# ColorfulTunes.net
KiCad netlist of a schematic drawn in EAGLE
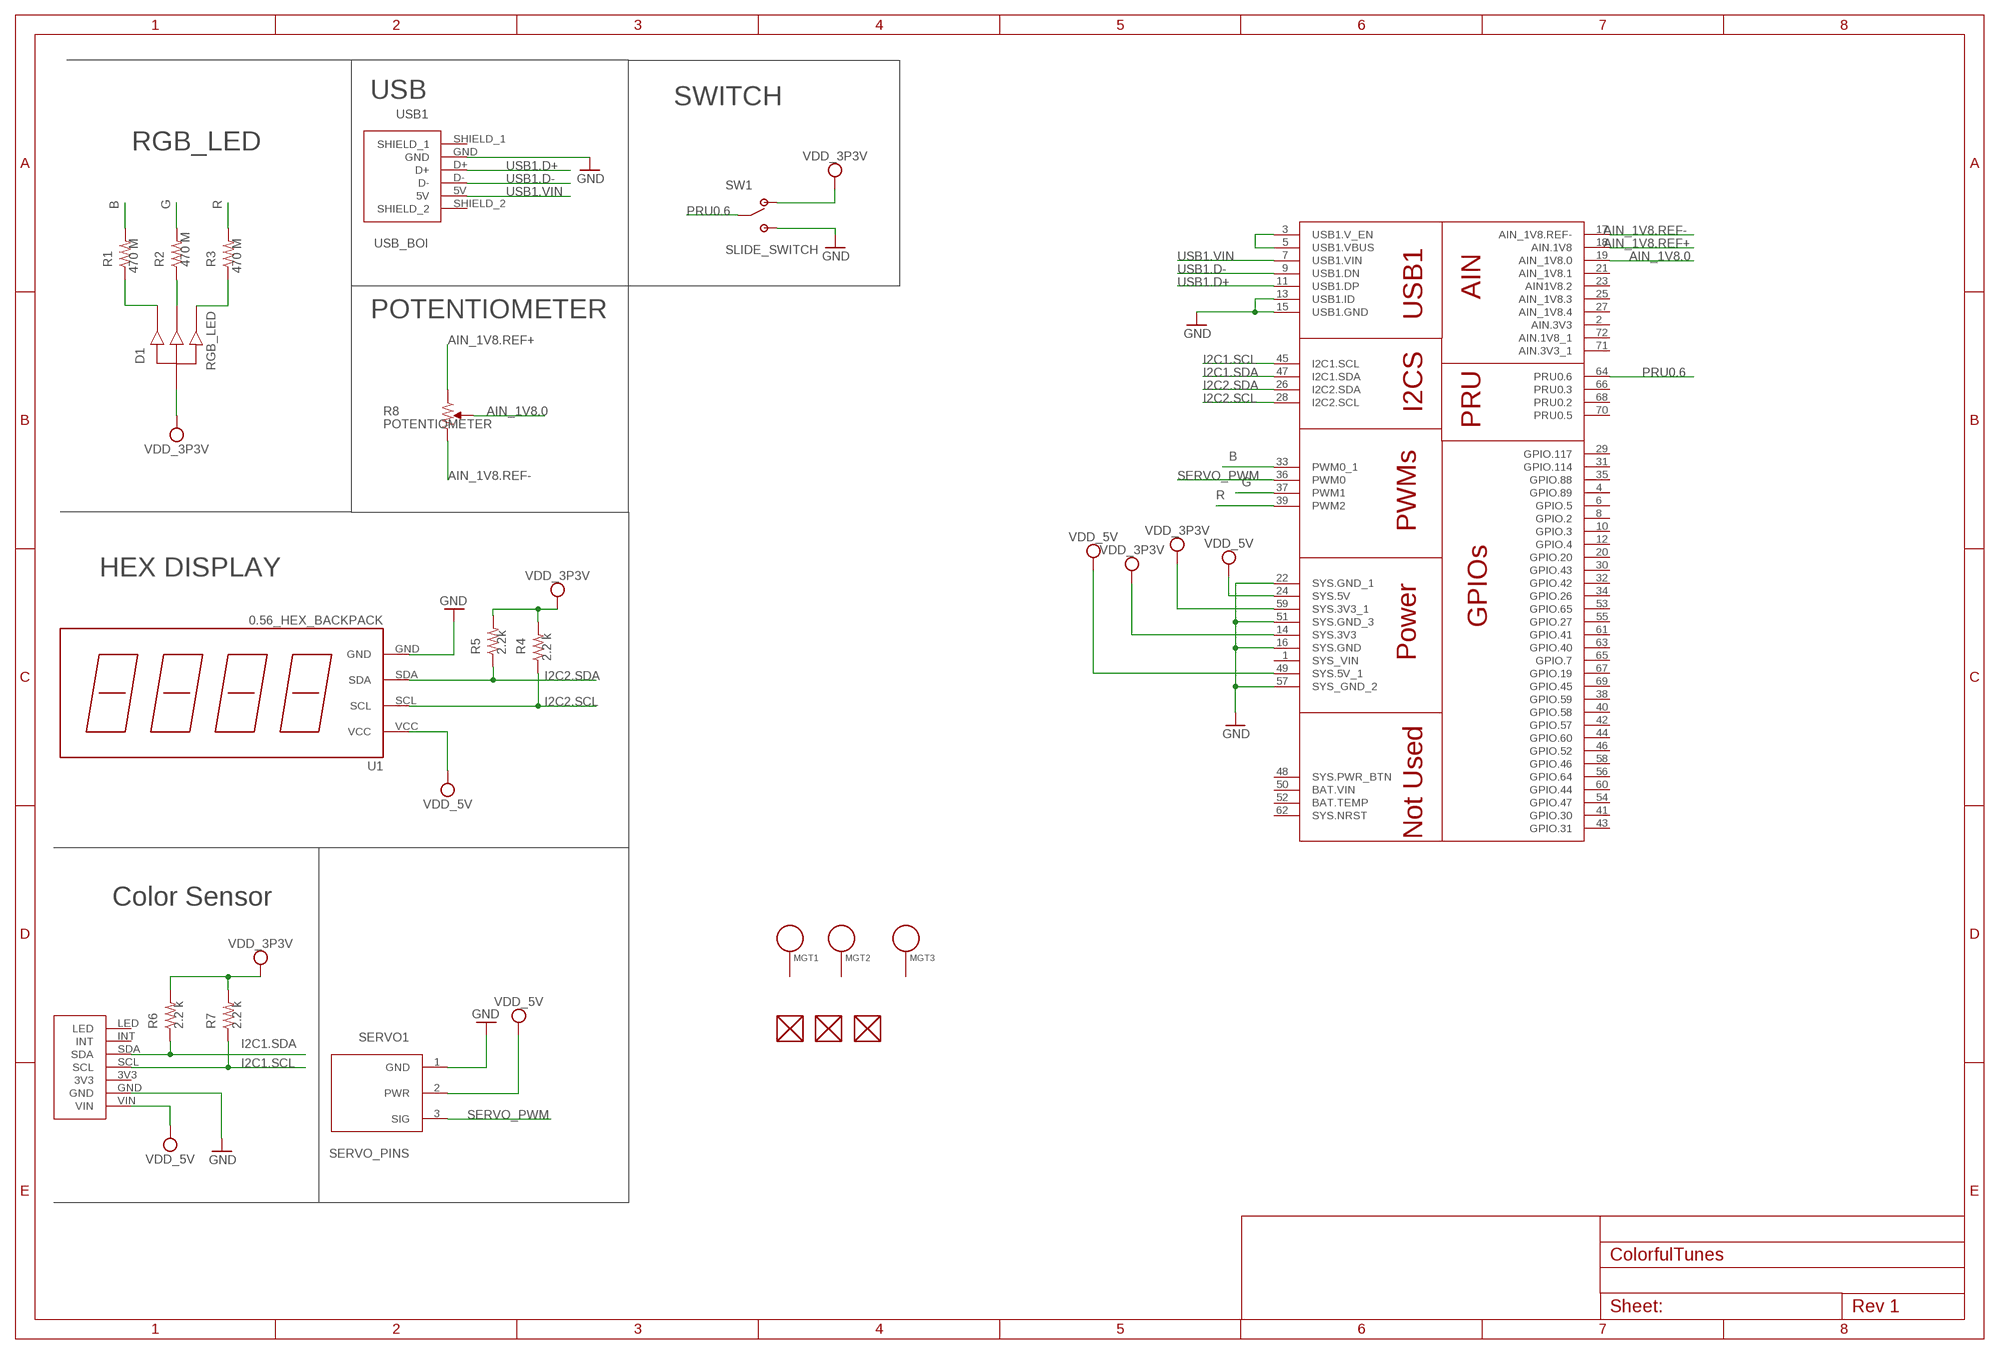
[diagram p0: schematic, sheet 1]

(export (version "E")
  (design (tool "Eeschema 10.0.6"))
  (components
    (comp (ref "CS1")
      (value "COLOR_SENSOR_PINS")
      (footprint "eagle-import:COLOR_SENSOR")
      (libsource (lib "eagle-import") (part "COLOR_SENSOR_PINS"))
    )
    (comp (ref "D1")
      (value "RGB_LED")
      (footprint "eagle-import:RGB_LED")
      (libsource (lib "eagle-import") (part "RGB_LED"))
    )
    (comp (ref "FUD1")
      (value "FIDUCIAL")
      (footprint "eagle-import:FIDUCIAL_40MIL")
      (libsource (lib "eagle-import") (part "FIDUCIAL"))
    )
    (comp (ref "FUD2")
      (value "FIDUCIAL")
      (footprint "eagle-import:FIDUCIAL_40MIL")
      (libsource (lib "eagle-import") (part "FIDUCIAL"))
    )
    (comp (ref "FUD3")
      (value "FIDUCIAL")
      (footprint "eagle-import:FIDUCIAL_40MIL")
      (libsource (lib "eagle-import") (part "FIDUCIAL"))
    )
    (comp (ref "MGT1")
      (value "MOUNTING_HOLE")
      (footprint "eagle-import:MOUNTING_HOLE")
      (libsource (lib "eagle-import") (part "MOUNTING_HOLE"))
    )
    (comp (ref "MGT2")
      (value "MOUNTING_HOLE")
      (footprint "eagle-import:MOUNTING_HOLE")
      (libsource (lib "eagle-import") (part "MOUNTING_HOLE"))
    )
    (comp (ref "MGT3")
      (value "MOUNTING_HOLE")
      (footprint "eagle-import:MOUNTING_HOLE")
      (libsource (lib "eagle-import") (part "MOUNTING_HOLE"))
    )
    (comp (ref "R1")
      (value "470 M")
      (footprint "eagle-import:R0402")
      (libsource (lib "eagle-import") (part "R_R0402"))
    )
    (comp (ref "R2")
      (value "470 M")
      (footprint "eagle-import:R0402")
      (libsource (lib "eagle-import") (part "R_R0402"))
    )
    (comp (ref "R3")
      (value "470 M")
      (footprint "eagle-import:R0402")
      (libsource (lib "eagle-import") (part "R_R0402"))
    )
    (comp (ref "R4")
      (value "2.2 k")
      (footprint "eagle-import:R0402")
      (libsource (lib "eagle-import") (part "R_R0402"))
    )
    (comp (ref "R5")
      (value "2.2k")
      (footprint "eagle-import:R0402")
      (libsource (lib "eagle-import") (part "R_R0402"))
    )
    (comp (ref "R6")
      (value "2.2 k")
      (footprint "eagle-import:R0402")
      (libsource (lib "eagle-import") (part "R_R0402"))
    )
    (comp (ref "R7")
      (value "2.2 k")
      (footprint "eagle-import:R0402")
      (libsource (lib "eagle-import") (part "R_R0402"))
    )
    (comp (ref "R8")
      (value "POTENTIOMETER")
      (footprint "eagle-import:POT-PO90S")
      (libsource (lib "eagle-import") (part "POTENTIOMETER"))
    )
    (comp (ref "SERVO1")
      (value "SERVO_PINS")
      (footprint "eagle-import:SERVO_PINS")
      (libsource (lib "eagle-import") (part "SERVO_PINS"))
    )
    (comp (ref "SW1")
      (value "SLIDE_SWITCH")
      (footprint "eagle-import:JS202011SCQN")
      (libsource (lib "eagle-import") (part "SLIDE_SWITCH"))
    )
    (comp (ref "U$1")
      (value "POCKET_BEAGLE")
      (footprint "eagle-import:POCKET_BEAGLE")
      (libsource (lib "eagle-import") (part "POCKET_BEAGLE"))
    )
    (comp (ref "U1")
      (value "0.56_HEX_BACKPACK")
      (footprint "eagle-import:0.56_HEX_BACKPACK")
      (libsource (lib "eagle-import") (part "0.56_HEX_BACKPACK"))
    )
    (comp (ref "USB1")
      (value "USB_BOI")
      (footprint "eagle-import:USB_BOI")
      (libsource (lib "eagle-import") (part "USB_BOI"))
    )
  )
  (nets
    (net (code "1") (name "/AIN_1V8.0") (class "Default")
      (node (ref "R8") (pin "S") (pinfunction "S_S") (pintype "bidirectional"))
      (node (ref "U$1") (pin "19") (pinfunction "AIN_1V8.0_19") (pintype "input"))
    )
    (net (code "2") (name "/AIN_1V8.REF+") (class "Default")
      (node (ref "R8") (pin "CCW") (pinfunction "CCW_CCW") (pintype "passive"))
      (node (ref "U$1") (pin "18") (pinfunction "AIN.1V8_18") (pintype "input"))
    )
    (net (code "3") (name "/AIN_1V8.REF-") (class "Default")
      (node (ref "R8") (pin "CW") (pinfunction "CW_CW") (pintype "passive"))
      (node (ref "U$1") (pin "17") (pinfunction "AIN_1V8.REF-_17") (pintype "input"))
    )
    (net (code "4") (name "/B") (class "Default")
      (node (ref "R1") (pin "2") (pinfunction "2_2") (pintype "passive"))
      (node (ref "U$1") (pin "33") (pinfunction "PWM0_1_33") (pintype "bidirectional"))
    )
    (net (code "5") (name "/G") (class "Default")
      (node (ref "R2") (pin "2") (pinfunction "2_2") (pintype "passive"))
      (node (ref "U$1") (pin "37") (pinfunction "PWM1_37") (pintype "bidirectional"))
    )
    (net (code "6") (name "/I2C1.SCL") (class "Default")
      (node (ref "CS1") (pin "SCL") (pinfunction "SCL_SCL") (pintype "bidirectional"))
      (node (ref "R7") (pin "1") (pinfunction "1_1") (pintype "passive"))
      (node (ref "U$1") (pin "45") (pinfunction "I2C1.SCL_45") (pintype "bidirectional"))
    )
    (net (code "7") (name "/I2C1.SDA") (class "Default")
      (node (ref "CS1") (pin "SDA") (pinfunction "SDA_SDA") (pintype "bidirectional"))
      (node (ref "R6") (pin "1") (pinfunction "1_1") (pintype "passive"))
      (node (ref "U$1") (pin "47") (pinfunction "I2C1.SDA_47") (pintype "bidirectional"))
    )
    (net (code "8") (name "/I2C2.SCL") (class "Default")
      (node (ref "R4") (pin "1") (pinfunction "1_1") (pintype "passive"))
      (node (ref "U$1") (pin "28") (pinfunction "I2C2.SCL_28") (pintype "bidirectional"))
      (node (ref "U1") (pin "SCL") (pinfunction "SCL_SCL") (pintype "bidirectional"))
    )
    (net (code "9") (name "/I2C2.SDA") (class "Default")
      (node (ref "R5") (pin "1") (pinfunction "1_1") (pintype "passive"))
      (node (ref "U$1") (pin "26") (pinfunction "I2C2.SDA_26") (pintype "bidirectional"))
      (node (ref "U1") (pin "SDA") (pinfunction "SDA_SDA") (pintype "bidirectional"))
    )
    (net (code "10") (name "/PRU0.6") (class "Default")
      (node (ref "SW1") (pin "2") (pinfunction "COMM_2") (pintype "bidirectional"))
      (node (ref "SW1") (pin "5") (pinfunction "COMM_5") (pintype "bidirectional"))
      (node (ref "U$1") (pin "64") (pinfunction "PRU0.6_64") (pintype "bidirectional"))
    )
    (net (code "11") (name "/R") (class "Default")
      (node (ref "R3") (pin "2") (pinfunction "2_2") (pintype "passive"))
      (node (ref "U$1") (pin "39") (pinfunction "PWM2_39") (pintype "bidirectional"))
    )
    (net (code "12") (name "/SERVO_PWM") (class "Default")
      (node (ref "SERVO1") (pin "3") (pinfunction "SIG_3") (pintype "bidirectional"))
      (node (ref "U$1") (pin "36") (pinfunction "PWM0_36") (pintype "bidirectional"))
    )
    (net (code "13") (name "/SYS_VIN") (class "Default")
      (node (ref "U$1") (pin "1") (pinfunction "SYS_VIN_1") (pintype "power_in"))
    )
    (net (code "14") (name "/USB1.D+") (class "Default")
      (node (ref "U$1") (pin "11") (pinfunction "USB1.DP_11") (pintype "bidirectional"))
      (node (ref "USB1") (pin "D+") (pinfunction "D+_D+") (pintype "bidirectional"))
    )
    (net (code "15") (name "/USB1.D-") (class "Default")
      (node (ref "U$1") (pin "9") (pinfunction "USB1.DN_9") (pintype "bidirectional"))
      (node (ref "USB1") (pin "D-") (pinfunction "D-_D-") (pintype "bidirectional"))
    )
    (net (code "16") (name "/USB1.VIN") (class "Default")
      (node (ref "U$1") (pin "7") (pinfunction "USB1.VIN_7") (pintype "bidirectional"))
      (node (ref "USB1") (pin "5V") (pinfunction "5V_5V") (pintype "bidirectional"))
    )
    (net (code "17") (name "GND") (class "Default")
      (node (ref "CS1") (pin "GND") (pinfunction "GND_GND") (pintype "bidirectional"))
      (node (ref "SERVO1") (pin "1") (pinfunction "GND_1") (pintype "bidirectional"))
      (node (ref "SW1") (pin "3") (pinfunction "POS2_3") (pintype "bidirectional"))
      (node (ref "SW1") (pin "6") (pinfunction "POS2_6") (pintype "bidirectional"))
      (node (ref "U$1") (pin "13") (pinfunction "USB1.ID_13") (pintype "bidirectional"))
      (node (ref "U$1") (pin "15") (pinfunction "USB1.GND_15") (pintype "bidirectional"))
      (node (ref "U$1") (pin "16") (pinfunction "SYS.GND_16") (pintype "bidirectional"))
      (node (ref "U$1") (pin "22") (pinfunction "SYS.GND_1_22") (pintype "power_in"))
      (node (ref "U$1") (pin "51") (pinfunction "SYS.GND_3_51") (pintype "power_in"))
      (node (ref "U$1") (pin "57") (pinfunction "SYS_GND_2_57") (pintype "bidirectional"))
      (node (ref "U1") (pin "GND") (pinfunction "GND_GND") (pintype "bidirectional"))
      (node (ref "USB1") (pin "GND") (pinfunction "GND_GND") (pintype "bidirectional"))
    )
    (net (code "18") (name "Net-(D1-PWM1)") (class "Default")
      (node (ref "D1") (pin "2") (pinfunction "PWM1_2") (pintype "bidirectional"))
      (node (ref "R1") (pin "1") (pinfunction "1_1") (pintype "passive"))
    )
    (net (code "19") (name "Net-(D1-PWM2)") (class "Default")
      (node (ref "D1") (pin "3") (pinfunction "PWM2_3") (pintype "bidirectional"))
      (node (ref "R2") (pin "1") (pinfunction "1_1") (pintype "passive"))
    )
    (net (code "20") (name "Net-(D1-PWM3)") (class "Default")
      (node (ref "D1") (pin "4") (pinfunction "PWM3_4") (pintype "bidirectional"))
      (node (ref "R3") (pin "1") (pinfunction "1_1") (pintype "passive"))
    )
    (net (code "21") (name "Net-(U$1-USB1.VBUS)") (class "Default")
      (node (ref "U$1") (pin "3") (pinfunction "USB1.V_EN_3") (pintype "bidirectional"))
      (node (ref "U$1") (pin "5") (pinfunction "USB1.VBUS_5") (pintype "bidirectional"))
    )
    (net (code "22") (name "VDD_3P3V") (class "Default")
      (node (ref "D1") (pin "1") (pinfunction "PWR_1") (pintype "power_in"))
      (node (ref "R4") (pin "2") (pinfunction "2_2") (pintype "passive"))
      (node (ref "R5") (pin "2") (pinfunction "2_2") (pintype "passive"))
      (node (ref "R6") (pin "2") (pinfunction "2_2") (pintype "passive"))
      (node (ref "R7") (pin "2") (pinfunction "2_2") (pintype "passive"))
      (node (ref "SW1") (pin "1") (pinfunction "POS1_1") (pintype "bidirectional"))
      (node (ref "SW1") (pin "4") (pinfunction "POS1_4") (pintype "bidirectional"))
      (node (ref "U$1") (pin "14") (pinfunction "SYS.3V3_14") (pintype "bidirectional"))
      (node (ref "U$1") (pin "59") (pinfunction "SYS.3V3_1_59") (pintype "power_in"))
    )
    (net (code "23") (name "VDD_5V") (class "Default")
      (node (ref "CS1") (pin "VIN") (pinfunction "VIN_VIN") (pintype "bidirectional"))
      (node (ref "SERVO1") (pin "2") (pinfunction "PWR_2") (pintype "bidirectional"))
      (node (ref "U$1") (pin "24") (pinfunction "SYS.5V_24") (pintype "power_in"))
      (node (ref "U$1") (pin "49") (pinfunction "SYS.5V_1_49") (pintype "power_in"))
      (node (ref "U1") (pin "VCC") (pinfunction "VCC_VCC") (pintype "power_in"))
    )
    (net (code "24") (name "unconnected-(CS1-Pad3V3)") (class "Default")
      (node (ref "CS1") (pin "3V3") (pinfunction "3V3_3V3") (pintype "bidirectional"))
    )
    (net (code "25") (name "unconnected-(CS1-PadINT)") (class "Default")
      (node (ref "CS1") (pin "INT") (pinfunction "INT_INT") (pintype "bidirectional"))
    )
    (net (code "26") (name "unconnected-(CS1-PadLED)") (class "Default")
      (node (ref "CS1") (pin "LED") (pinfunction "LED_LED") (pintype "bidirectional"))
    )
    (net (code "27") (name "unconnected-(FUD1-PadP$1)") (class "Default")
      (node (ref "FUD1") (pin "P$1") (pinfunction "P$1_P$1") (pintype "no_connect"))
    )
    (net (code "28") (name "unconnected-(FUD2-PadP$1)") (class "Default")
      (node (ref "FUD2") (pin "P$1") (pinfunction "P$1_P$1") (pintype "no_connect"))
    )
    (net (code "29") (name "unconnected-(FUD3-PadP$1)") (class "Default")
      (node (ref "FUD3") (pin "P$1") (pinfunction "P$1_P$1") (pintype "no_connect"))
    )
    (net (code "30") (name "unconnected-(MGT1-PadP$1)") (class "Default")
      (node (ref "MGT1") (pin "P$1") (pinfunction "P$1_P$1") (pintype "bidirectional"))
    )
    (net (code "31") (name "unconnected-(MGT2-PadP$1)") (class "Default")
      (node (ref "MGT2") (pin "P$1") (pinfunction "P$1_P$1") (pintype "bidirectional"))
    )
    (net (code "32") (name "unconnected-(MGT3-PadP$1)") (class "Default")
      (node (ref "MGT3") (pin "P$1") (pinfunction "P$1_P$1") (pintype "bidirectional"))
    )
    (net (code "33") (name "unconnected-(U$1-AIN.1V8_1-Pad72)") (class "Default")
      (node (ref "U$1") (pin "72") (pinfunction "AIN.1V8_1_72") (pintype "bidirectional"))
    )
    (net (code "34") (name "unconnected-(U$1-AIN.3V3-Pad2)") (class "Default")
      (node (ref "U$1") (pin "2") (pinfunction "AIN.3V3_2") (pintype "input"))
    )
    (net (code "35") (name "unconnected-(U$1-AIN.3V3_1-Pad71)") (class "Default")
      (node (ref "U$1") (pin "71") (pinfunction "AIN.3V3_1_71") (pintype "bidirectional"))
    )
    (net (code "36") (name "unconnected-(U$1-AIN1V8.2-Pad23)") (class "Default")
      (node (ref "U$1") (pin "23") (pinfunction "AIN1V8.2_23") (pintype "bidirectional"))
    )
    (net (code "37") (name "unconnected-(U$1-AIN_1V8.1-Pad21)") (class "Default")
      (node (ref "U$1") (pin "21") (pinfunction "AIN_1V8.1_21") (pintype "bidirectional"))
    )
    (net (code "38") (name "unconnected-(U$1-AIN_1V8.3-Pad25)") (class "Default")
      (node (ref "U$1") (pin "25") (pinfunction "AIN_1V8.3_25") (pintype "bidirectional"))
    )
    (net (code "39") (name "unconnected-(U$1-AIN_1V8.4-Pad27)") (class "Default")
      (node (ref "U$1") (pin "27") (pinfunction "AIN_1V8.4_27") (pintype "bidirectional"))
    )
    (net (code "40") (name "unconnected-(U$1-BAT.TEMP-Pad52)") (class "Default")
      (node (ref "U$1") (pin "52") (pinfunction "BAT.TEMP_52") (pintype "bidirectional"))
    )
    (net (code "41") (name "unconnected-(U$1-BAT.VIN-Pad50)") (class "Default")
      (node (ref "U$1") (pin "50") (pinfunction "BAT.VIN_50") (pintype "bidirectional"))
    )
    (net (code "42") (name "unconnected-(U$1-GPIO.2-Pad8)") (class "Default")
      (node (ref "U$1") (pin "8") (pinfunction "GPIO.2_8") (pintype "bidirectional"))
    )
    (net (code "43") (name "unconnected-(U$1-GPIO.3-Pad10)") (class "Default")
      (node (ref "U$1") (pin "10") (pinfunction "GPIO.3_10") (pintype "bidirectional"))
    )
    (net (code "44") (name "unconnected-(U$1-GPIO.4-Pad12)") (class "Default")
      (node (ref "U$1") (pin "12") (pinfunction "GPIO.4_12") (pintype "bidirectional"))
    )
    (net (code "45") (name "unconnected-(U$1-GPIO.5-Pad6)") (class "Default")
      (node (ref "U$1") (pin "6") (pinfunction "GPIO.5_6") (pintype "bidirectional"))
    )
    (net (code "46") (name "unconnected-(U$1-GPIO.7-Pad65)") (class "Default")
      (node (ref "U$1") (pin "65") (pinfunction "GPIO.7_65") (pintype "bidirectional"))
    )
    (net (code "47") (name "unconnected-(U$1-GPIO.19-Pad67)") (class "Default")
      (node (ref "U$1") (pin "67") (pinfunction "GPIO.19_67") (pintype "bidirectional"))
    )
    (net (code "48") (name "unconnected-(U$1-GPIO.20-Pad20)") (class "Default")
      (node (ref "U$1") (pin "20") (pinfunction "GPIO.20_20") (pintype "bidirectional"))
    )
    (net (code "49") (name "unconnected-(U$1-GPIO.26-Pad34)") (class "Default")
      (node (ref "U$1") (pin "34") (pinfunction "GPIO.26_34") (pintype "bidirectional"))
    )
    (net (code "50") (name "unconnected-(U$1-GPIO.27-Pad55)") (class "Default")
      (node (ref "U$1") (pin "55") (pinfunction "GPIO.27_55") (pintype "bidirectional"))
    )
    (net (code "51") (name "unconnected-(U$1-GPIO.30-Pad41)") (class "Default")
      (node (ref "U$1") (pin "41") (pinfunction "GPIO.30_41") (pintype "bidirectional"))
    )
    (net (code "52") (name "unconnected-(U$1-GPIO.31-Pad43)") (class "Default")
      (node (ref "U$1") (pin "43") (pinfunction "GPIO.31_43") (pintype "bidirectional"))
    )
    (net (code "53") (name "unconnected-(U$1-GPIO.40-Pad63)") (class "Default")
      (node (ref "U$1") (pin "63") (pinfunction "GPIO.40_63") (pintype "bidirectional"))
    )
    (net (code "54") (name "unconnected-(U$1-GPIO.41-Pad61)") (class "Default")
      (node (ref "U$1") (pin "61") (pinfunction "GPIO.41_61") (pintype "bidirectional"))
    )
    (net (code "55") (name "unconnected-(U$1-GPIO.42-Pad32)") (class "Default")
      (node (ref "U$1") (pin "32") (pinfunction "GPIO.42_32") (pintype "bidirectional"))
    )
    (net (code "56") (name "unconnected-(U$1-GPIO.43-Pad30)") (class "Default")
      (node (ref "U$1") (pin "30") (pinfunction "GPIO.43_30") (pintype "bidirectional"))
    )
    (net (code "57") (name "unconnected-(U$1-GPIO.44-Pad60)") (class "Default")
      (node (ref "U$1") (pin "60") (pinfunction "GPIO.44_60") (pintype "bidirectional"))
    )
    (net (code "58") (name "unconnected-(U$1-GPIO.45-Pad69)") (class "Default")
      (node (ref "U$1") (pin "69") (pinfunction "GPIO.45_69") (pintype "bidirectional"))
    )
    (net (code "59") (name "unconnected-(U$1-GPIO.46-Pad58)") (class "Default")
      (node (ref "U$1") (pin "58") (pinfunction "GPIO.46_58") (pintype "bidirectional"))
    )
    (net (code "60") (name "unconnected-(U$1-GPIO.47-Pad54)") (class "Default")
      (node (ref "U$1") (pin "54") (pinfunction "GPIO.47_54") (pintype "bidirectional"))
    )
    (net (code "61") (name "unconnected-(U$1-GPIO.52-Pad46)") (class "Default")
      (node (ref "U$1") (pin "46") (pinfunction "GPIO.52_46") (pintype "bidirectional"))
    )
    (net (code "62") (name "unconnected-(U$1-GPIO.57-Pad42)") (class "Default")
      (node (ref "U$1") (pin "42") (pinfunction "GPIO.57_42") (pintype "bidirectional"))
    )
    (net (code "63") (name "unconnected-(U$1-GPIO.58-Pad40)") (class "Default")
      (node (ref "U$1") (pin "40") (pinfunction "GPIO.58_40") (pintype "bidirectional"))
    )
    (net (code "64") (name "unconnected-(U$1-GPIO.59-Pad38)") (class "Default")
      (node (ref "U$1") (pin "38") (pinfunction "GPIO.59_38") (pintype "bidirectional"))
    )
    (net (code "65") (name "unconnected-(U$1-GPIO.60-Pad44)") (class "Default")
      (node (ref "U$1") (pin "44") (pinfunction "GPIO.60_44") (pintype "bidirectional"))
    )
    (net (code "66") (name "unconnected-(U$1-GPIO.64-Pad56)") (class "Default")
      (node (ref "U$1") (pin "56") (pinfunction "GPIO.64_56") (pintype "bidirectional"))
    )
    (net (code "67") (name "unconnected-(U$1-GPIO.65-Pad53)") (class "Default")
      (node (ref "U$1") (pin "53") (pinfunction "GPIO.65_53") (pintype "bidirectional"))
    )
    (net (code "68") (name "unconnected-(U$1-GPIO.88-Pad35)") (class "Default")
      (node (ref "U$1") (pin "35") (pinfunction "GPIO.88_35") (pintype "bidirectional"))
    )
    (net (code "69") (name "unconnected-(U$1-GPIO.89-Pad4)") (class "Default")
      (node (ref "U$1") (pin "4") (pinfunction "GPIO.89_4") (pintype "bidirectional"))
    )
    (net (code "70") (name "unconnected-(U$1-GPIO.114-Pad31)") (class "Default")
      (node (ref "U$1") (pin "31") (pinfunction "GPIO.114_31") (pintype "bidirectional"))
    )
    (net (code "71") (name "unconnected-(U$1-GPIO.117-Pad29)") (class "Default")
      (node (ref "U$1") (pin "29") (pinfunction "GPIO.117_29") (pintype "bidirectional"))
    )
    (net (code "72") (name "unconnected-(U$1-PRU0.2-Pad68)") (class "Default")
      (node (ref "U$1") (pin "68") (pinfunction "PRU0.2_68") (pintype "bidirectional"))
    )
    (net (code "73") (name "unconnected-(U$1-PRU0.3-Pad66)") (class "Default")
      (node (ref "U$1") (pin "66") (pinfunction "PRU0.3_66") (pintype "bidirectional"))
    )
    (net (code "74") (name "unconnected-(U$1-PRU0.5-Pad70)") (class "Default")
      (node (ref "U$1") (pin "70") (pinfunction "PRU0.5_70") (pintype "bidirectional"))
    )
    (net (code "75") (name "unconnected-(U$1-SYS.NRST-Pad62)") (class "Default")
      (node (ref "U$1") (pin "62") (pinfunction "SYS.NRST_62") (pintype "bidirectional"))
    )
    (net (code "76") (name "unconnected-(U$1-SYS.PWR_BTN-Pad48)") (class "Default")
      (node (ref "U$1") (pin "48") (pinfunction "SYS.PWR_BTN_48") (pintype "bidirectional"))
    )
    (net (code "77") (name "unconnected-(USB1-PadSHIELD_1)") (class "Default")
      (node (ref "USB1") (pin "SHIELD_1") (pinfunction "SHIELD_1_SHIELD_1") (pintype "bidirectional"))
    )
    (net (code "78") (name "unconnected-(USB1-PadSHIELD_2)") (class "Default")
      (node (ref "USB1") (pin "SHIELD_2") (pinfunction "SHIELD_2_SHIELD_2") (pintype "bidirectional"))
    )
  )
)
